# lcd.net
KiCad netlist of a schematic drawn in Altium Designer
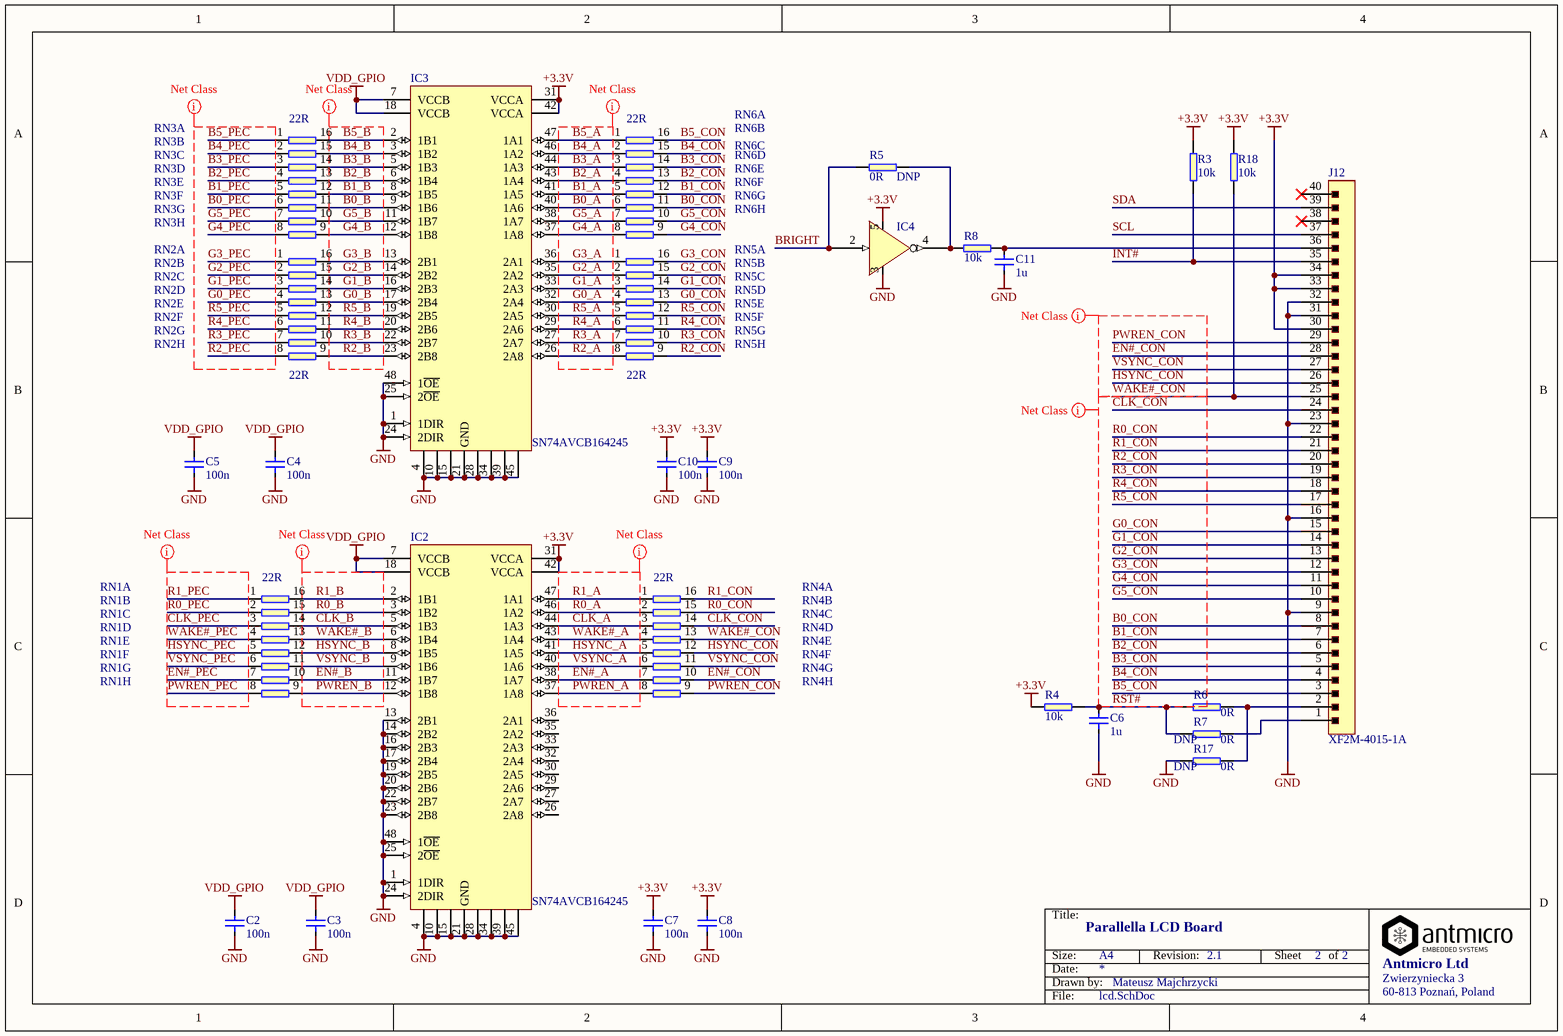
[diagram p0: lcd.SchDoc]

(export (version "E")
  (design (tool "Eeschema 10.0.6"))
  (components
    (comp (ref "C2")
      (value "100n")
      (footprint "0603")
      (description "MLCC SMT Capacitor 100nF 0603")
      (fields (field (name "PART NUMBER") "C_100n_0603") (field (name "TOLERANCE") "5%"))
      (libsource (lib "AntmicroComponents") (part "C"))
    )
    (comp (ref "C3")
      (value "100n")
      (footprint "0603")
      (description "MLCC SMT Capacitor 100nF 0603")
      (fields (field (name "PART NUMBER") "C_100n_0603") (field (name "TOLERANCE") "5%"))
      (libsource (lib "AntmicroComponents") (part "C"))
    )
    (comp (ref "C4")
      (value "100n")
      (footprint "0603")
      (description "MLCC SMT Capacitor 100nF 0603")
      (fields (field (name "PART NUMBER") "C_100n_0603") (field (name "TOLERANCE") "5%"))
      (libsource (lib "AntmicroComponents") (part "C"))
    )
    (comp (ref "C5")
      (value "100n")
      (footprint "0603")
      (description "MLCC SMT Capacitor 100nF 0603")
      (fields (field (name "PART NUMBER") "C_100n_0603") (field (name "TOLERANCE") "5%"))
      (libsource (lib "AntmicroComponents") (part "C"))
    )
    (comp (ref "C6")
      (value "1u")
      (footprint "0603")
      (description "MLCC SMT Capacitor 1uF 0603")
      (fields (field (name "PART NUMBER") "C_1u_0603"))
      (libsource (lib "AntmicroComponents") (part "C"))
    )
    (comp (ref "C7")
      (value "100n")
      (footprint "0603")
      (description "MLCC SMT Capacitor 100nF 0603")
      (fields (field (name "PART NUMBER") "C_100n_0603") (field (name "TOLERANCE") "5%"))
      (libsource (lib "AntmicroComponents") (part "C"))
    )
    (comp (ref "C8")
      (value "100n")
      (footprint "0603")
      (description "MLCC SMT Capacitor 100nF 0603")
      (fields (field (name "PART NUMBER") "C_100n_0603") (field (name "TOLERANCE") "5%"))
      (libsource (lib "AntmicroComponents") (part "C"))
    )
    (comp (ref "C9")
      (value "100n")
      (footprint "0603")
      (description "MLCC SMT Capacitor 100nF 0603")
      (fields (field (name "PART NUMBER") "C_100n_0603") (field (name "TOLERANCE") "5%"))
      (libsource (lib "AntmicroComponents") (part "C"))
    )
    (comp (ref "C10")
      (value "100n")
      (footprint "0603")
      (description "MLCC SMT Capacitor 100nF 0603")
      (fields (field (name "PART NUMBER") "C_100n_0603") (field (name "TOLERANCE") "5%"))
      (libsource (lib "AntmicroComponents") (part "C"))
    )
    (comp (ref "C11")
      (value "1u")
      (footprint "0603")
      (description "MLCC SMT Capacitor 1uF 0603")
      (fields (field (name "PART NUMBER") "C_1u_0603"))
      (libsource (lib "AntmicroComponents") (part "C"))
    )
    (comp (ref "IC2")
      (value "SN74AVCB164245")
      (footprint "TSSOP40P640X120-48N")
      (description "SN74AVCB164245GR - IC, NON INVERTING TRANSCEIVER, TSSOP-48")
      (fields (field (name "PART NUMBER") "SN74AVCB164245GR"))
      (libsource (lib "AntmicroComponents") (part "SN74AVCB164245"))
    )
    (comp (ref "IC3")
      (value "SN74AVCB164245")
      (footprint "TSSOP40P640X120-48N")
      (description "SN74AVCB164245GR - IC, NON INVERTING TRANSCEIVER, TSSOP-48")
      (fields (field (name "PART NUMBER") "SN74AVCB164245GR"))
      (libsource (lib "AntmicroComponents") (part "SN74AVCB164245"))
    )
    (comp (ref "IC4")
      (value "SN74AUC1G04")
      (footprint "SC70-5")
      (description "LOGIC, INVERTER GATE, SC-70-5")
      (libsource (lib "AntmicroComponents") (part "SN74AUC1G04"))
    )
    (comp (ref "J12")
      (value "XF2M-4015-1A")
      (footprint "XF2M-4015-1A")
      (description "RECEPTACLE, FPC, ZIF, SMT, 0.5MM, 40WAY")
      (libsource (lib "AntmicroComponents") (part "XF2M-4015-1A"))
    )
    (comp (ref "R3")
      (value "10k")
      (footprint "0603")
      (description "SMT Resistor 10k 0603")
      (fields (field (name "PART NUMBER") "R_10k_0603"))
      (libsource (lib "") (part "R_2"))
    )
    (comp (ref "R4")
      (value "10k")
      (footprint "0603")
      (description "SMT Resistor 10k 0603")
      (fields (field (name "PART NUMBER") "R_10k_0603"))
      (libsource (lib "") (part "R_1"))
    )
    (comp (ref "R5")
      (value "DNP")
      (footprint "0603")
      (description "SMT Resistor 0R 0603")
      (fields
        (field (name "ALTIUM_VALUE") "0R")
        (field (name "PART NUMBER") "R_0R_0603")
        (field (name "TOLERANCE") "5%")
      )
      (libsource (lib "AntmicroComponents") (part "R"))
    )
    (comp (ref "R6")
      (value "0R")
      (footprint "0603")
      (description "SMT Resistor 0R 0603")
      (fields (field (name "PART NUMBER") "R_0R_0603") (field (name "TOLERANCE") "5%"))
      (libsource (lib "") (part "R_1"))
    )
    (comp (ref "R7")
      (value "DNP")
      (footprint "0603")
      (description "SMT Resistor 0R 0603")
      (fields
        (field (name "ALTIUM_VALUE") "0R")
        (field (name "PART NUMBER") "R_0R_0603")
        (field (name "TOLERANCE") "5%")
      )
      (libsource (lib "") (part "R_1"))
    )
    (comp (ref "R8")
      (value "10k")
      (footprint "0603")
      (description "SMT Resistor 10k 0603")
      (fields (field (name "PART NUMBER") "R_10k_0603"))
      (libsource (lib "AntmicroComponents") (part "R"))
    )
    (comp (ref "R17")
      (value "DNP")
      (footprint "0603")
      (description "SMT Resistor 0R 0603")
      (fields
        (field (name "ALTIUM_VALUE") "0R")
        (field (name "PART NUMBER") "R_0R_0603")
        (field (name "TOLERANCE") "5%")
      )
      (libsource (lib "") (part "R_1"))
    )
    (comp (ref "R18")
      (value "10k")
      (footprint "0603")
      (description "SMT Resistor 10k 0603")
      (fields (field (name "PART NUMBER") "R_10k_0603"))
      (libsource (lib "") (part "R_2"))
    )
    (comp (ref "RN1")
      (value "22R")
      (footprint "EXB2HV")
      (description "Resistor network 8x0402")
      (fields (field (name "PART NUMBER") "Rnet22R"))
      (libsource (lib "AntmicroComponents") (part "EXB2HV"))
    )
    (comp (ref "RN2")
      (value "22R")
      (footprint "EXB2HV")
      (description "Resistor network 8x0402")
      (fields (field (name "PART NUMBER") "Rnet22R"))
      (libsource (lib "AntmicroComponents") (part "EXB2HV"))
    )
    (comp (ref "RN3")
      (value "22R")
      (footprint "EXB2HV")
      (description "Resistor network 8x0402")
      (fields (field (name "PART NUMBER") "Rnet22R"))
      (libsource (lib "AntmicroComponents") (part "EXB2HV"))
    )
    (comp (ref "RN4")
      (value "22R")
      (footprint "EXB2HV")
      (description "Resistor network 8x0402")
      (fields (field (name "PART NUMBER") "Rnet22R"))
      (libsource (lib "AntmicroComponents") (part "EXB2HV"))
    )
    (comp (ref "RN5")
      (value "22R")
      (footprint "EXB2HV")
      (description "Resistor network 8x0402")
      (fields (field (name "PART NUMBER") "Rnet22R"))
      (libsource (lib "AntmicroComponents") (part "EXB2HV"))
    )
    (comp (ref "RN6")
      (value "22R")
      (footprint "EXB2HV")
      (description "Resistor network 8x0402")
      (fields (field (name "PART NUMBER") "Rnet22R"))
      (libsource (lib "AntmicroComponents") (part "EXB2HV"))
    )
  )
  (nets
    (net (code "1") (name "+3.3V") (class "Default")
      (node (ref "C10") (pin "2") (pinfunction "2_2") (pintype "passive"))
      (node (ref "C7") (pin "2") (pinfunction "2_2") (pintype "passive"))
      (node (ref "C8") (pin "2") (pinfunction "2_2") (pintype "passive"))
      (node (ref "C9") (pin "2") (pinfunction "2_2") (pintype "passive"))
      (node (ref "IC2") (pin "31") (pinfunction "VCCA_31") (pintype "power_in"))
      (node (ref "IC2") (pin "42") (pinfunction "VCCA_42") (pintype "power_in"))
      (node (ref "IC3") (pin "31") (pinfunction "VCCA_31") (pintype "power_in"))
      (node (ref "IC3") (pin "42") (pinfunction "VCCA_42") (pintype "power_in"))
      (node (ref "IC4") (pin "5") (pinfunction "VCC_5") (pintype "power_in"))
      (node (ref "J12") (pin "30") (pinfunction "30_30") (pintype "passive"))
      (node (ref "J12") (pin "33") (pinfunction "33_33") (pintype "passive"))
      (node (ref "J12") (pin "34") (pinfunction "34_34") (pintype "passive"))
      (node (ref "R18") (pin "2") (pintype "passive"))
      (node (ref "R3") (pin "2") (pintype "passive"))
      (node (ref "R4") (pin "1") (pintype "passive"))
    )
    (net (code "2") (name "/B0_A") (class "Default")
      (node (ref "IC3") (pin "40") (pinfunction "1A6_40") (pintype "bidirectional"))
      (node (ref "RN6") (pin "6") (pintype "passive"))
    )
    (net (code "3") (name "/B0_B") (class "Default")
      (node (ref "IC3") (pin "9") (pinfunction "1B6_9") (pintype "bidirectional"))
      (node (ref "RN3") (pin "11") (pintype "passive"))
    )
    (net (code "4") (name "/B0_CON") (class "Default")
      (node (ref "J12") (pin "8") (pinfunction "8_8") (pintype "passive"))
      (node (ref "RN6") (pin "11") (pintype "passive"))
    )
    (net (code "5") (name "/B0_PEC") (class "Default") (node (ref "RN3") (pin "6") (pintype "passive")))
    (net (code "6") (name "/B1_A") (class "Default")
      (node (ref "IC3") (pin "41") (pinfunction "1A5_41") (pintype "bidirectional"))
      (node (ref "RN6") (pin "5") (pintype "passive"))
    )
    (net (code "7") (name "/B1_B") (class "Default")
      (node (ref "IC3") (pin "8") (pinfunction "1B5_8") (pintype "bidirectional"))
      (node (ref "RN3") (pin "12") (pintype "passive"))
    )
    (net (code "8") (name "/B1_CON") (class "Default")
      (node (ref "J12") (pin "7") (pinfunction "7_7") (pintype "passive"))
      (node (ref "RN6") (pin "12") (pintype "passive"))
    )
    (net (code "9") (name "/B1_PEC") (class "Default") (node (ref "RN3") (pin "5") (pintype "passive")))
    (net (code "10") (name "/B2_A") (class "Default")
      (node (ref "IC3") (pin "43") (pinfunction "1A4_43") (pintype "bidirectional"))
      (node (ref "RN6") (pin "4") (pintype "passive"))
    )
    (net (code "11") (name "/B2_B") (class "Default")
      (node (ref "IC3") (pin "6") (pinfunction "1B4_6") (pintype "bidirectional"))
      (node (ref "RN3") (pin "13") (pintype "passive"))
    )
    (net (code "12") (name "/B2_CON") (class "Default")
      (node (ref "J12") (pin "6") (pinfunction "6_6") (pintype "passive"))
      (node (ref "RN6") (pin "13") (pintype "passive"))
    )
    (net (code "13") (name "/B2_PEC") (class "Default") (node (ref "RN3") (pin "4") (pintype "passive")))
    (net (code "14") (name "/B3_A") (class "Default")
      (node (ref "IC3") (pin "44") (pinfunction "1A3_44") (pintype "bidirectional"))
      (node (ref "RN6") (pin "3") (pintype "passive"))
    )
    (net (code "15") (name "/B3_B") (class "Default")
      (node (ref "IC3") (pin "5") (pinfunction "1B3_5") (pintype "bidirectional"))
      (node (ref "RN3") (pin "14") (pintype "passive"))
    )
    (net (code "16") (name "/B3_CON") (class "Default")
      (node (ref "J12") (pin "5") (pinfunction "5_5") (pintype "passive"))
      (node (ref "RN6") (pin "14") (pintype "passive"))
    )
    (net (code "17") (name "/B3_PEC") (class "Default") (node (ref "RN3") (pin "3") (pintype "passive")))
    (net (code "18") (name "/B4_A") (class "Default")
      (node (ref "IC3") (pin "46") (pinfunction "1A2_46") (pintype "bidirectional"))
      (node (ref "RN6") (pin "2") (pintype "passive"))
    )
    (net (code "19") (name "/B4_B") (class "Default")
      (node (ref "IC3") (pin "3") (pinfunction "1B2_3") (pintype "bidirectional"))
      (node (ref "RN3") (pin "15") (pintype "passive"))
    )
    (net (code "20") (name "/B4_CON") (class "Default")
      (node (ref "J12") (pin "4") (pinfunction "4_4") (pintype "passive"))
      (node (ref "RN6") (pin "15") (pintype "passive"))
    )
    (net (code "21") (name "/B4_PEC") (class "Default") (node (ref "RN3") (pin "2") (pintype "passive")))
    (net (code "22") (name "/B5_A") (class "Default")
      (node (ref "IC3") (pin "47") (pinfunction "1A1_47") (pintype "bidirectional"))
      (node (ref "RN6") (pin "1") (pintype "passive"))
    )
    (net (code "23") (name "/B5_B") (class "Default")
      (node (ref "IC3") (pin "2") (pinfunction "1B1_2") (pintype "bidirectional"))
      (node (ref "RN3") (pin "16") (pintype "passive"))
    )
    (net (code "24") (name "/B5_CON") (class "Default")
      (node (ref "J12") (pin "3") (pinfunction "3_3") (pintype "passive"))
      (node (ref "RN6") (pin "16") (pintype "passive"))
    )
    (net (code "25") (name "/B5_PEC") (class "Default") (node (ref "RN3") (pin "1") (pintype "passive")))
    (net (code "26") (name "/BRIGHT") (class "Default")
      (node (ref "IC4") (pin "2") (pinfunction "IN_2") (pintype "input"))
      (node (ref "R5") (pin "2") (pintype "passive"))
    )
    (net (code "27") (name "/CLK_A") (class "Default")
      (node (ref "IC2") (pin "44") (pinfunction "1A3_44") (pintype "bidirectional"))
      (node (ref "RN4") (pin "3") (pintype "passive"))
    )
    (net (code "28") (name "/CLK_B") (class "Default")
      (node (ref "IC2") (pin "5") (pinfunction "1B3_5") (pintype "bidirectional"))
      (node (ref "RN1") (pin "14") (pintype "passive"))
    )
    (net (code "29") (name "/CLK_CON") (class "Default")
      (node (ref "J12") (pin "24") (pinfunction "24_24") (pintype "passive"))
      (node (ref "RN4") (pin "14") (pintype "passive"))
    )
    (net (code "30") (name "/CLK_PEC") (class "Default") (node (ref "RN1") (pin "3") (pintype "passive")))
    (net (code "31") (name "/EN#_A") (class "Default")
      (node (ref "IC2") (pin "38") (pinfunction "1A7_38") (pintype "bidirectional"))
      (node (ref "RN4") (pin "7") (pintype "passive"))
    )
    (net (code "32") (name "/EN#_B") (class "Default")
      (node (ref "IC2") (pin "11") (pinfunction "1B7_11") (pintype "bidirectional"))
      (node (ref "RN1") (pin "10") (pintype "passive"))
    )
    (net (code "33") (name "/EN#_CON") (class "Default")
      (node (ref "J12") (pin "28") (pinfunction "28_28") (pintype "passive"))
      (node (ref "RN4") (pin "10") (pintype "passive"))
    )
    (net (code "34") (name "/EN#_PEC") (class "Default") (node (ref "RN1") (pin "7") (pintype "passive")))
    (net (code "35") (name "/G0_A") (class "Default")
      (node (ref "IC3") (pin "32") (pinfunction "2A4_32") (pintype "bidirectional"))
      (node (ref "RN5") (pin "4") (pintype "passive"))
    )
    (net (code "36") (name "/G0_B") (class "Default")
      (node (ref "IC3") (pin "17") (pinfunction "2B4_17") (pintype "bidirectional"))
      (node (ref "RN2") (pin "13") (pintype "passive"))
    )
    (net (code "37") (name "/G0_CON") (class "Default")
      (node (ref "J12") (pin "15") (pinfunction "15_15") (pintype "passive"))
      (node (ref "RN5") (pin "13") (pintype "passive"))
    )
    (net (code "38") (name "/G0_PEC") (class "Default") (node (ref "RN2") (pin "4") (pintype "passive")))
    (net (code "39") (name "/G1_A") (class "Default")
      (node (ref "IC3") (pin "33") (pinfunction "2A3_33") (pintype "bidirectional"))
      (node (ref "RN5") (pin "3") (pintype "passive"))
    )
    (net (code "40") (name "/G1_B") (class "Default")
      (node (ref "IC3") (pin "16") (pinfunction "2B3_16") (pintype "bidirectional"))
      (node (ref "RN2") (pin "14") (pintype "passive"))
    )
    (net (code "41") (name "/G1_CON") (class "Default")
      (node (ref "J12") (pin "14") (pinfunction "14_14") (pintype "passive"))
      (node (ref "RN5") (pin "14") (pintype "passive"))
    )
    (net (code "42") (name "/G1_PEC") (class "Default") (node (ref "RN2") (pin "3") (pintype "passive")))
    (net (code "43") (name "/G2_A") (class "Default")
      (node (ref "IC3") (pin "35") (pinfunction "2A2_35") (pintype "bidirectional"))
      (node (ref "RN5") (pin "2") (pintype "passive"))
    )
    (net (code "44") (name "/G2_B") (class "Default")
      (node (ref "IC3") (pin "14") (pinfunction "2B2_14") (pintype "bidirectional"))
      (node (ref "RN2") (pin "15") (pintype "passive"))
    )
    (net (code "45") (name "/G2_CON") (class "Default")
      (node (ref "J12") (pin "13") (pinfunction "13_13") (pintype "passive"))
      (node (ref "RN5") (pin "15") (pintype "passive"))
    )
    (net (code "46") (name "/G2_PEC") (class "Default") (node (ref "RN2") (pin "2") (pintype "passive")))
    (net (code "47") (name "/G3_A") (class "Default")
      (node (ref "IC3") (pin "36") (pinfunction "2A1_36") (pintype "bidirectional"))
      (node (ref "RN5") (pin "1") (pintype "passive"))
    )
    (net (code "48") (name "/G3_B") (class "Default")
      (node (ref "IC3") (pin "13") (pinfunction "2B1_13") (pintype "bidirectional"))
      (node (ref "RN2") (pin "16") (pintype "passive"))
    )
    (net (code "49") (name "/G3_CON") (class "Default")
      (node (ref "J12") (pin "12") (pinfunction "12_12") (pintype "passive"))
      (node (ref "RN5") (pin "16") (pintype "passive"))
    )
    (net (code "50") (name "/G3_PEC") (class "Default") (node (ref "RN2") (pin "1") (pintype "passive")))
    (net (code "51") (name "/G4_A") (class "Default")
      (node (ref "IC3") (pin "37") (pinfunction "1A8_37") (pintype "bidirectional"))
      (node (ref "RN6") (pin "8") (pintype "passive"))
    )
    (net (code "52") (name "/G4_B") (class "Default")
      (node (ref "IC3") (pin "12") (pinfunction "1B8_12") (pintype "bidirectional"))
      (node (ref "RN3") (pin "9") (pintype "passive"))
    )
    (net (code "53") (name "/G4_CON") (class "Default")
      (node (ref "J12") (pin "11") (pinfunction "11_11") (pintype "passive"))
      (node (ref "RN6") (pin "9") (pintype "passive"))
    )
    (net (code "54") (name "/G4_PEC") (class "Default") (node (ref "RN3") (pin "8") (pintype "passive")))
    (net (code "55") (name "/G5_A") (class "Default")
      (node (ref "IC3") (pin "38") (pinfunction "1A7_38") (pintype "bidirectional"))
      (node (ref "RN6") (pin "7") (pintype "passive"))
    )
    (net (code "56") (name "/G5_B") (class "Default")
      (node (ref "IC3") (pin "11") (pinfunction "1B7_11") (pintype "bidirectional"))
      (node (ref "RN3") (pin "10") (pintype "passive"))
    )
    (net (code "57") (name "/G5_CON") (class "Default")
      (node (ref "J12") (pin "10") (pinfunction "10_10") (pintype "passive"))
      (node (ref "RN6") (pin "10") (pintype "passive"))
    )
    (net (code "58") (name "/G5_PEC") (class "Default") (node (ref "RN3") (pin "7") (pintype "passive")))
    (net (code "59") (name "/HSYNC_A") (class "Default")
      (node (ref "IC2") (pin "41") (pinfunction "1A5_41") (pintype "bidirectional"))
      (node (ref "RN4") (pin "5") (pintype "passive"))
    )
    (net (code "60") (name "/HSYNC_B") (class "Default")
      (node (ref "IC2") (pin "8") (pinfunction "1B5_8") (pintype "bidirectional"))
      (node (ref "RN1") (pin "12") (pintype "passive"))
    )
    (net (code "61") (name "/HSYNC_CON") (class "Default")
      (node (ref "J12") (pin "26") (pinfunction "26_26") (pintype "passive"))
      (node (ref "RN4") (pin "12") (pintype "passive"))
    )
    (net (code "62") (name "/HSYNC_PEC") (class "Default") (node (ref "RN1") (pin "5") (pintype "passive")))
    (net (code "63") (name "/INT#") (class "Default")
      (node (ref "J12") (pin "35") (pinfunction "35_35") (pintype "passive"))
      (node (ref "R3") (pin "1") (pintype "passive"))
    )
    (net (code "64") (name "/PWREN_A") (class "Default")
      (node (ref "IC2") (pin "37") (pinfunction "1A8_37") (pintype "bidirectional"))
      (node (ref "RN4") (pin "8") (pintype "passive"))
    )
    (net (code "65") (name "/PWREN_B") (class "Default")
      (node (ref "IC2") (pin "12") (pinfunction "1B8_12") (pintype "bidirectional"))
      (node (ref "RN1") (pin "9") (pintype "passive"))
    )
    (net (code "66") (name "/PWREN_CON") (class "Default")
      (node (ref "J12") (pin "29") (pinfunction "29_29") (pintype "passive"))
      (node (ref "RN4") (pin "9") (pintype "passive"))
    )
    (net (code "67") (name "/PWREN_PEC") (class "Default") (node (ref "RN1") (pin "8") (pintype "passive")))
    (net (code "68") (name "/R0_A") (class "Default")
      (node (ref "IC2") (pin "46") (pinfunction "1A2_46") (pintype "bidirectional"))
      (node (ref "RN4") (pin "2") (pintype "passive"))
    )
    (net (code "69") (name "/R0_B") (class "Default")
      (node (ref "IC2") (pin "3") (pinfunction "1B2_3") (pintype "bidirectional"))
      (node (ref "RN1") (pin "15") (pintype "passive"))
    )
    (net (code "70") (name "/R0_CON") (class "Default")
      (node (ref "J12") (pin "22") (pinfunction "22_22") (pintype "passive"))
      (node (ref "RN4") (pin "15") (pintype "passive"))
    )
    (net (code "71") (name "/R0_PEC") (class "Default") (node (ref "RN1") (pin "2") (pintype "passive")))
    (net (code "72") (name "/R1_A") (class "Default")
      (node (ref "IC2") (pin "47") (pinfunction "1A1_47") (pintype "bidirectional"))
      (node (ref "RN4") (pin "1") (pintype "passive"))
    )
    (net (code "73") (name "/R1_B") (class "Default")
      (node (ref "IC2") (pin "2") (pinfunction "1B1_2") (pintype "bidirectional"))
      (node (ref "RN1") (pin "16") (pintype "passive"))
    )
    (net (code "74") (name "/R1_CON") (class "Default")
      (node (ref "J12") (pin "21") (pinfunction "21_21") (pintype "passive"))
      (node (ref "RN4") (pin "16") (pintype "passive"))
    )
    (net (code "75") (name "/R1_PEC") (class "Default") (node (ref "RN1") (pin "1") (pintype "passive")))
    (net (code "76") (name "/R2_A") (class "Default")
      (node (ref "IC3") (pin "26") (pinfunction "2A8_26") (pintype "bidirectional"))
      (node (ref "RN5") (pin "8") (pintype "passive"))
    )
    (net (code "77") (name "/R2_B") (class "Default")
      (node (ref "IC3") (pin "23") (pinfunction "2B8_23") (pintype "bidirectional"))
      (node (ref "RN2") (pin "9") (pintype "passive"))
    )
    (net (code "78") (name "/R2_CON") (class "Default")
      (node (ref "J12") (pin "20") (pinfunction "20_20") (pintype "passive"))
      (node (ref "RN5") (pin "9") (pintype "passive"))
    )
    (net (code "79") (name "/R2_PEC") (class "Default") (node (ref "RN2") (pin "8") (pintype "passive")))
    (net (code "80") (name "/R3_A") (class "Default")
      (node (ref "IC3") (pin "27") (pinfunction "2A7_27") (pintype "bidirectional"))
      (node (ref "RN5") (pin "7") (pintype "passive"))
    )
    (net (code "81") (name "/R3_B") (class "Default")
      (node (ref "IC3") (pin "22") (pinfunction "2B7_22") (pintype "bidirectional"))
      (node (ref "RN2") (pin "10") (pintype "passive"))
    )
    (net (code "82") (name "/R3_CON") (class "Default")
      (node (ref "J12") (pin "19") (pinfunction "19_19") (pintype "passive"))
      (node (ref "RN5") (pin "10") (pintype "passive"))
    )
    (net (code "83") (name "/R3_PEC") (class "Default") (node (ref "RN2") (pin "7") (pintype "passive")))
    (net (code "84") (name "/R4_A") (class "Default")
      (node (ref "IC3") (pin "29") (pinfunction "2A6_29") (pintype "bidirectional"))
      (node (ref "RN5") (pin "6") (pintype "passive"))
    )
    (net (code "85") (name "/R4_B") (class "Default")
      (node (ref "IC3") (pin "20") (pinfunction "2B6_20") (pintype "bidirectional"))
      (node (ref "RN2") (pin "11") (pintype "passive"))
    )
    (net (code "86") (name "/R4_CON") (class "Default")
      (node (ref "J12") (pin "18") (pinfunction "18_18") (pintype "passive"))
      (node (ref "RN5") (pin "11") (pintype "passive"))
    )
    (net (code "87") (name "/R4_PEC") (class "Default") (node (ref "RN2") (pin "6") (pintype "passive")))
    (net (code "88") (name "/R5_A") (class "Default")
      (node (ref "IC3") (pin "30") (pinfunction "2A5_30") (pintype "bidirectional"))
      (node (ref "RN5") (pin "5") (pintype "passive"))
    )
    (net (code "89") (name "/R5_B") (class "Default")
      (node (ref "IC3") (pin "19") (pinfunction "2B5_19") (pintype "bidirectional"))
      (node (ref "RN2") (pin "12") (pintype "passive"))
    )
    (net (code "90") (name "/R5_CON") (class "Default")
      (node (ref "J12") (pin "17") (pinfunction "17_17") (pintype "passive"))
      (node (ref "RN5") (pin "12") (pintype "passive"))
    )
    (net (code "91") (name "/R5_PEC") (class "Default") (node (ref "RN2") (pin "5") (pintype "passive")))
    (net (code "92") (name "/RST#") (class "Default")
      (node (ref "C6") (pin "2") (pinfunction "2_2") (pintype "passive"))
      (node (ref "R4") (pin "2") (pintype "passive"))
      (node (ref "R6") (pin "1") (pintype "passive"))
      (node (ref "R7") (pin "1") (pintype "passive"))
    )
    (net (code "93") (name "/SCL") (class "Default")
      (node (ref "J12") (pin "37") (pinfunction "37_37") (pintype "passive"))
    )
    (net (code "94") (name "/SDA") (class "Default")
      (node (ref "J12") (pin "39") (pinfunction "39_39") (pintype "passive"))
    )
    (net (code "95") (name "/VSYNC_A") (class "Default")
      (node (ref "IC2") (pin "40") (pinfunction "1A6_40") (pintype "bidirectional"))
      (node (ref "RN4") (pin "6") (pintype "passive"))
    )
    (net (code "96") (name "/VSYNC_B") (class "Default")
      (node (ref "IC2") (pin "9") (pinfunction "1B6_9") (pintype "bidirectional"))
      (node (ref "RN1") (pin "11") (pintype "passive"))
    )
    (net (code "97") (name "/VSYNC_CON") (class "Default")
      (node (ref "J12") (pin "27") (pinfunction "27_27") (pintype "passive"))
      (node (ref "RN4") (pin "11") (pintype "passive"))
    )
    (net (code "98") (name "/VSYNC_PEC") (class "Default") (node (ref "RN1") (pin "6") (pintype "passive")))
    (net (code "99") (name "/WAKE#_A") (class "Default")
      (node (ref "IC2") (pin "43") (pinfunction "1A4_43") (pintype "bidirectional"))
      (node (ref "RN4") (pin "4") (pintype "passive"))
    )
    (net (code "100") (name "/WAKE#_B") (class "Default")
      (node (ref "IC2") (pin "6") (pinfunction "1B4_6") (pintype "bidirectional"))
      (node (ref "RN1") (pin "13") (pintype "passive"))
    )
    (net (code "101") (name "/WAKE#_CON") (class "Default")
      (node (ref "J12") (pin "25") (pinfunction "25_25") (pintype "passive"))
      (node (ref "R18") (pin "1") (pintype "passive"))
      (node (ref "RN4") (pin "13") (pintype "passive"))
    )
    (net (code "102") (name "/WAKE#_PEC") (class "Default") (node (ref "RN1") (pin "4") (pintype "passive")))
    (net (code "103") (name "GND") (class "Default")
      (node (ref "C10") (pin "1") (pinfunction "1_1") (pintype "passive"))
      (node (ref "C11") (pin "1") (pinfunction "1_1") (pintype "passive"))
      (node (ref "C2") (pin "1") (pinfunction "1_1") (pintype "passive"))
      (node (ref "C3") (pin "1") (pinfunction "1_1") (pintype "passive"))
      (node (ref "C4") (pin "1") (pinfunction "1_1") (pintype "passive"))
      (node (ref "C5") (pin "1") (pinfunction "1_1") (pintype "passive"))
      (node (ref "C6") (pin "1") (pinfunction "1_1") (pintype "passive"))
      (node (ref "C7") (pin "1") (pinfunction "1_1") (pintype "passive"))
      (node (ref "C8") (pin "1") (pinfunction "1_1") (pintype "passive"))
      (node (ref "C9") (pin "1") (pinfunction "1_1") (pintype "passive"))
      (node (ref "IC2") (pin "1") (pinfunction "1DIR_1") (pintype "input"))
      (node (ref "IC2") (pin "10") (pinfunction "GND_10") (pintype "power_in"))
      (node (ref "IC2") (pin "13") (pinfunction "2B1_13") (pintype "bidirectional"))
      (node (ref "IC2") (pin "14") (pinfunction "2B2_14") (pintype "bidirectional"))
      (node (ref "IC2") (pin "15") (pinfunction "GND_15") (pintype "power_in"))
      (node (ref "IC2") (pin "16") (pinfunction "2B3_16") (pintype "bidirectional"))
      (node (ref "IC2") (pin "17") (pinfunction "2B4_17") (pintype "bidirectional"))
      (node (ref "IC2") (pin "19") (pinfunction "2B5_19") (pintype "bidirectional"))
      (node (ref "IC2") (pin "20") (pinfunction "2B6_20") (pintype "bidirectional"))
      (node (ref "IC2") (pin "21") (pinfunction "GND_21") (pintype "power_in"))
      (node (ref "IC2") (pin "22") (pinfunction "2B7_22") (pintype "bidirectional"))
      (node (ref "IC2") (pin "23") (pinfunction "2B8_23") (pintype "bidirectional"))
      (node (ref "IC2") (pin "24") (pinfunction "2DIR_24") (pintype "input"))
      (node (ref "IC2") (pin "25") (pinfunction "2~{OE}_25") (pintype "input"))
      (node (ref "IC2") (pin "28") (pinfunction "GND_28") (pintype "power_in"))
      (node (ref "IC2") (pin "34") (pinfunction "GND_34") (pintype "power_in"))
      (node (ref "IC2") (pin "39") (pinfunction "GND_39") (pintype "power_in"))
      (node (ref "IC2") (pin "4") (pinfunction "GND_4") (pintype "power_in"))
      (node (ref "IC2") (pin "45") (pinfunction "GND_45") (pintype "power_in"))
      (node (ref "IC2") (pin "48") (pinfunction "1~{OE}_48") (pintype "input"))
      (node (ref "IC3") (pin "1") (pinfunction "1DIR_1") (pintype "input"))
      (node (ref "IC3") (pin "10") (pinfunction "GND_10") (pintype "power_in"))
      (node (ref "IC3") (pin "15") (pinfunction "GND_15") (pintype "power_in"))
      (node (ref "IC3") (pin "21") (pinfunction "GND_21") (pintype "power_in"))
      (node (ref "IC3") (pin "24") (pinfunction "2DIR_24") (pintype "input"))
      (node (ref "IC3") (pin "25") (pinfunction "2~{OE}_25") (pintype "input"))
      (node (ref "IC3") (pin "28") (pinfunction "GND_28") (pintype "power_in"))
      (node (ref "IC3") (pin "34") (pinfunction "GND_34") (pintype "power_in"))
      (node (ref "IC3") (pin "39") (pinfunction "GND_39") (pintype "power_in"))
      (node (ref "IC3") (pin "4") (pinfunction "GND_4") (pintype "power_in"))
      (node (ref "IC3") (pin "45") (pinfunction "GND_45") (pintype "power_in"))
      (node (ref "IC3") (pin "48") (pinfunction "1~{OE}_48") (pintype "input"))
      (node (ref "IC4") (pin "3") (pinfunction "GND_3") (pintype "power_in"))
      (node (ref "J12") (pin "16") (pinfunction "16_16") (pintype "passive"))
      (node (ref "J12") (pin "23") (pinfunction "23_23") (pintype "passive"))
      (node (ref "J12") (pin "31") (pinfunction "31_31") (pintype "passive"))
      (node (ref "J12") (pin "32") (pinfunction "32_32") (pintype "passive"))
      (node (ref "J12") (pin "9") (pinfunction "9_9") (pintype "passive"))
      (node (ref "R17") (pin "1") (pintype "passive"))
    )
    (net (code "104") (name "Net-(C11-Pad2)") (class "Default")
      (node (ref "C11") (pin "2") (pinfunction "2_2") (pintype "passive"))
      (node (ref "J12") (pin "36") (pinfunction "36_36") (pintype "passive"))
      (node (ref "R8") (pin "1") (pintype "passive"))
    )
    (net (code "105") (name "Net-(IC4-OUT)") (class "Default")
      (node (ref "IC4") (pin "4") (pinfunction "OUT_4") (pintype "output"))
      (node (ref "R5") (pin "1") (pintype "passive"))
      (node (ref "R8") (pin "2") (pintype "passive"))
    )
    (net (code "106") (name "Net-(J12-Pad1)") (class "Default")
      (node (ref "J12") (pin "1") (pinfunction "1_1") (pintype "passive"))
      (node (ref "R7") (pin "2") (pintype "passive"))
    )
    (net (code "107") (name "Net-(J12-Pad2)") (class "Default")
      (node (ref "J12") (pin "2") (pinfunction "2_2") (pintype "passive"))
      (node (ref "R17") (pin "2") (pintype "passive"))
      (node (ref "R6") (pin "2") (pintype "passive"))
    )
    (net (code "108") (name "VDD_GPIO") (class "Default")
      (node (ref "C2") (pin "2") (pinfunction "2_2") (pintype "passive"))
      (node (ref "C3") (pin "2") (pinfunction "2_2") (pintype "passive"))
      (node (ref "C4") (pin "2") (pinfunction "2_2") (pintype "passive"))
      (node (ref "C5") (pin "2") (pinfunction "2_2") (pintype "passive"))
      (node (ref "IC2") (pin "18") (pinfunction "VCCB_18") (pintype "power_in"))
      (node (ref "IC2") (pin "7") (pinfunction "VCCB_7") (pintype "power_in"))
      (node (ref "IC3") (pin "18") (pinfunction "VCCB_18") (pintype "power_in"))
      (node (ref "IC3") (pin "7") (pinfunction "VCCB_7") (pintype "power_in"))
    )
    (net (code "109") (name "unconnected-(IC2-2A1-Pad36)") (class "Default")
      (node (ref "IC2") (pin "36") (pinfunction "2A1_36") (pintype "bidirectional"))
    )
    (net (code "110") (name "unconnected-(IC2-2A2-Pad35)") (class "Default")
      (node (ref "IC2") (pin "35") (pinfunction "2A2_35") (pintype "bidirectional"))
    )
    (net (code "111") (name "unconnected-(IC2-2A3-Pad33)") (class "Default")
      (node (ref "IC2") (pin "33") (pinfunction "2A3_33") (pintype "bidirectional"))
    )
    (net (code "112") (name "unconnected-(IC2-2A4-Pad32)") (class "Default")
      (node (ref "IC2") (pin "32") (pinfunction "2A4_32") (pintype "bidirectional"))
    )
    (net (code "113") (name "unconnected-(IC2-2A5-Pad30)") (class "Default")
      (node (ref "IC2") (pin "30") (pinfunction "2A5_30") (pintype "bidirectional"))
    )
    (net (code "114") (name "unconnected-(IC2-2A6-Pad29)") (class "Default")
      (node (ref "IC2") (pin "29") (pinfunction "2A6_29") (pintype "bidirectional"))
    )
    (net (code "115") (name "unconnected-(IC2-2A7-Pad27)") (class "Default")
      (node (ref "IC2") (pin "27") (pinfunction "2A7_27") (pintype "bidirectional"))
    )
    (net (code "116") (name "unconnected-(IC2-2A8-Pad26)") (class "Default")
      (node (ref "IC2") (pin "26") (pinfunction "2A8_26") (pintype "bidirectional"))
    )
    (net (code "117") (name "unconnected-(J12-Pad38)") (class "Default")
      (node (ref "J12") (pin "38") (pinfunction "38_38") (pintype "passive+no_connect"))
    )
    (net (code "118") (name "unconnected-(J12-Pad40)") (class "Default")
      (node (ref "J12") (pin "40") (pinfunction "40_40") (pintype "passive+no_connect"))
    )
  )
)
